# Button.net
KiCad netlist of a schematic drawn in Altium Designer
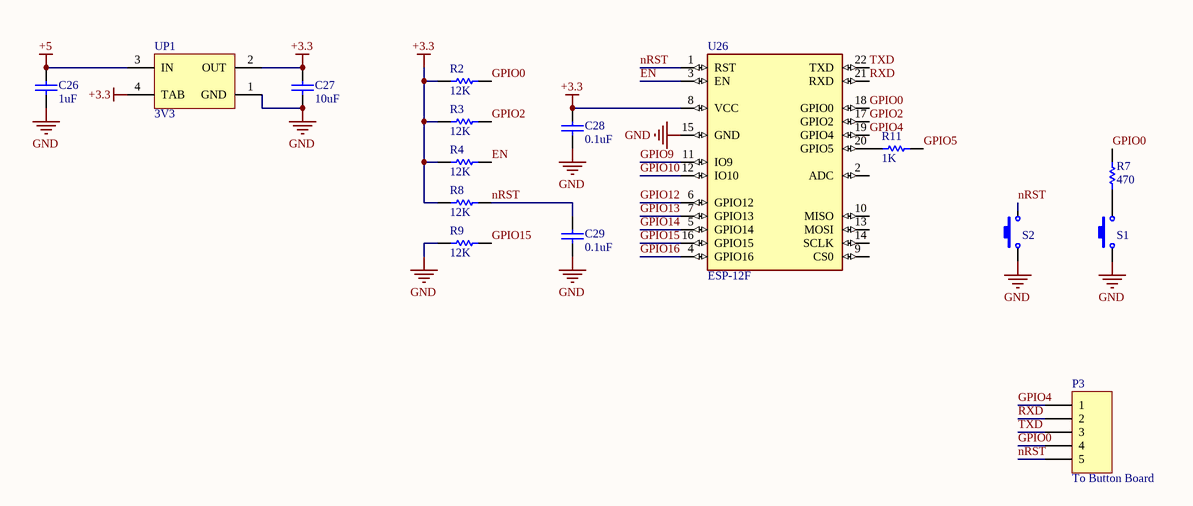
[diagram p0: Button.SchDoc]

(export (version "E")
  (design (tool "Eeschema 10.0.6"))
  (components
    (comp (ref "C26")
      (value "1uF")
      (footprint "CAPC3413X12N")
      (description "CAP 0805")
      (fields (field (name "DESIGNER") "Abbas Basereh"))
      (libsource (lib "Altium") (part "CAP SMD 0805"))
    )
    (comp (ref "C27")
      (value "10uF")
      (footprint "CAPC3413X12N")
      (description "CAP 0805")
      (fields (field (name "DESIGNER") "Abbas Basereh"))
      (libsource (lib "Altium") (part "CAP SMD 0805"))
    )
    (comp (ref "C28")
      (value "0.1uF")
      (footprint "CAPC3413X12N")
      (description "CAP 0805")
      (fields (field (name "DESIGNER") "Abbas Basereh"))
      (libsource (lib "Altium") (part "CAP SMD 0805"))
    )
    (comp (ref "C29")
      (value "0.1uF")
      (footprint "CAPC3413X12N")
      (description "CAP 0805")
      (fields (field (name "DESIGNER") "Abbas Basereh"))
      (libsource (lib "Altium") (part "CAP SMD 0805"))
    )
    (comp (ref "P3")
      (value "To Button Board")
      (footprint "HDR1X5")
      (description "Header, 5-Pin")
      (fields (field (name "PUBLISHER") "Altium Limited"))
      (libsource (lib "Altium") (part "Header 5"))
    )
    (comp (ref "R2")
      (value "12K")
      (footprint "RES0805")
      (description "TOTAL SMD RESISTOR PACK")
      (fields (field (name "DESIGNER") "Abbas Basereh"))
      (libsource (lib "Altium") (part "RES SMD PACKAGE"))
    )
    (comp (ref "R3")
      (value "12K")
      (footprint "RES0805")
      (description "TOTAL SMD RESISTOR PACK")
      (fields (field (name "DESIGNER") "Abbas Basereh"))
      (libsource (lib "Altium") (part "RES SMD PACKAGE"))
    )
    (comp (ref "R4")
      (value "12K")
      (footprint "RES0805")
      (description "TOTAL SMD RESISTOR PACK")
      (fields (field (name "DESIGNER") "Abbas Basereh"))
      (libsource (lib "Altium") (part "RES SMD PACKAGE"))
    )
    (comp (ref "R7")
      (value "470")
      (footprint "RES0805")
      (description "TOTAL SMD RESISTOR PACK")
      (fields (field (name "DESIGNER") "Abbas Basereh"))
      (libsource (lib "Altium") (part "RES SMD PACKAGE"))
    )
    (comp (ref "R8")
      (value "12K")
      (footprint "RES0805")
      (description "TOTAL SMD RESISTOR PACK")
      (fields (field (name "DESIGNER") "Abbas Basereh"))
      (libsource (lib "Altium") (part "RES SMD PACKAGE"))
    )
    (comp (ref "R9")
      (value "12K")
      (footprint "RES0805")
      (description "TOTAL SMD RESISTOR PACK")
      (fields (field (name "DESIGNER") "Abbas Basereh"))
      (libsource (lib "Altium") (part "RES SMD PACKAGE"))
    )
    (comp (ref "R11")
      (value "1K")
      (footprint "RES0805")
      (description "TOTAL SMD RESISTOR PACK")
      (fields (field (name "DESIGNER") "Abbas Basereh"))
      (libsource (lib "Altium") (part "RES SMD PACKAGE"))
    )
    (comp (ref "S1")
      (value "Switch PB")
      (footprint "SW-PB")
      (description "Push Button Switch")
      (libsource (lib "Altium") (part "Switch PB"))
    )
    (comp (ref "S2")
      (value "Switch PB")
      (footprint "SW-PB")
      (description "Push Button Switch")
      (libsource (lib "Altium") (part "Switch PB"))
    )
    (comp (ref "U26")
      (value "ESP-12F")
      (footprint "ESP-12F")
      (description "WiFi Module")
      (fields (field (name "MF") "AI-Thinker"))
      (libsource (lib "ESP-12F") (part "ESP-12F"))
    )
    (comp (ref "UP1")
      (value "3V3")
      (footprint "SOT223")
      (description "x.x Volt, 800mA Low-Dropout Linear Regulator, 4-pin SOT-223")
      (fields (field (name "DESIGNER") "Ali Hafizi"))
      (libsource (lib "Altium") (part "AMS1117-x.x"))
    )
  )
  (nets
    (net (code "1") (name "+3.3") (class "Default")
      (node (ref "C27") (pin "1") (pinfunction "1_1") (pintype "passive"))
      (node (ref "C28") (pin "1") (pinfunction "1_1") (pintype "passive"))
      (node (ref "R2") (pin "1") (pinfunction "1_1") (pintype "passive"))
      (node (ref "R3") (pin "1") (pinfunction "1_1") (pintype "passive"))
      (node (ref "R4") (pin "1") (pinfunction "1_1") (pintype "passive"))
      (node (ref "R8") (pin "1") (pinfunction "1_1") (pintype "passive"))
      (node (ref "U26") (pin "8") (pinfunction "VCC_8") (pintype "bidirectional"))
      (node (ref "UP1") (pin "2") (pinfunction "OUT_2") (pintype "power_in"))
      (node (ref "UP1") (pin "4") (pinfunction "TAB_4") (pintype "power_in"))
    )
    (net (code "2") (name "+5") (class "Default")
      (node (ref "C26") (pin "1") (pinfunction "1_1") (pintype "passive"))
      (node (ref "UP1") (pin "3") (pinfunction "IN_3") (pintype "power_in"))
    )
    (net (code "3") (name "/EN") (class "Default")
      (node (ref "R4") (pin "2") (pinfunction "2_2") (pintype "passive"))
      (node (ref "U26") (pin "3") (pinfunction "EN_3") (pintype "bidirectional"))
    )
    (net (code "4") (name "/GPIO0") (class "Default")
      (node (ref "P3") (pin "4") (pinfunction "4_4") (pintype "passive"))
      (node (ref "R2") (pin "2") (pinfunction "2_2") (pintype "passive"))
      (node (ref "R7") (pin "1") (pinfunction "1_1") (pintype "passive"))
      (node (ref "U26") (pin "18") (pinfunction "GPIO0_18") (pintype "bidirectional"))
    )
    (net (code "5") (name "/GPIO2") (class "Default")
      (node (ref "R3") (pin "2") (pinfunction "2_2") (pintype "passive"))
      (node (ref "U26") (pin "17") (pinfunction "GPIO2_17") (pintype "bidirectional"))
    )
    (net (code "6") (name "/GPIO4") (class "Default")
      (node (ref "P3") (pin "1") (pinfunction "1_1") (pintype "passive"))
      (node (ref "U26") (pin "19") (pinfunction "GPIO4_19") (pintype "bidirectional"))
    )
    (net (code "7") (name "/GPIO5") (class "Default")
      (node (ref "R11") (pin "2") (pinfunction "2_2") (pintype "passive"))
    )
    (net (code "8") (name "/GPIO9") (class "Default")
      (node (ref "U26") (pin "11") (pinfunction "IO9_11") (pintype "bidirectional"))
    )
    (net (code "9") (name "/GPIO10") (class "Default")
      (node (ref "U26") (pin "12") (pinfunction "IO10_12") (pintype "bidirectional"))
    )
    (net (code "10") (name "/GPIO12") (class "Default")
      (node (ref "U26") (pin "6") (pinfunction "GPIO12_6") (pintype "bidirectional"))
    )
    (net (code "11") (name "/GPIO13") (class "Default")
      (node (ref "U26") (pin "7") (pinfunction "GPIO13_7") (pintype "bidirectional"))
    )
    (net (code "12") (name "/GPIO14") (class "Default")
      (node (ref "U26") (pin "5") (pinfunction "GPIO14_5") (pintype "bidirectional"))
    )
    (net (code "13") (name "/GPIO15") (class "Default")
      (node (ref "R9") (pin "2") (pinfunction "2_2") (pintype "passive"))
      (node (ref "U26") (pin "16") (pinfunction "GPIO15_16") (pintype "bidirectional"))
    )
    (net (code "14") (name "/GPIO16") (class "Default")
      (node (ref "U26") (pin "4") (pinfunction "GPIO16_4") (pintype "bidirectional"))
    )
    (net (code "15") (name "/RXD") (class "Default")
      (node (ref "P3") (pin "2") (pinfunction "2_2") (pintype "passive"))
      (node (ref "U26") (pin "21") (pinfunction "RXD_21") (pintype "bidirectional"))
    )
    (net (code "16") (name "/TXD") (class "Default")
      (node (ref "P3") (pin "3") (pinfunction "3_3") (pintype "passive"))
      (node (ref "U26") (pin "22") (pinfunction "TXD_22") (pintype "bidirectional"))
    )
    (net (code "17") (name "/nRST") (class "Default")
      (node (ref "C29") (pin "2") (pinfunction "2_2") (pintype "passive"))
      (node (ref "P3") (pin "5") (pinfunction "5_5") (pintype "passive"))
      (node (ref "R8") (pin "2") (pinfunction "2_2") (pintype "passive"))
      (node (ref "S2") (pin "2") (pinfunction "2_2") (pintype "passive"))
      (node (ref "U26") (pin "1") (pinfunction "RST_1") (pintype "bidirectional"))
    )
    (net (code "18") (name "GND") (class "Default")
      (node (ref "C26") (pin "2") (pinfunction "2_2") (pintype "passive"))
      (node (ref "C27") (pin "2") (pinfunction "2_2") (pintype "passive"))
      (node (ref "C28") (pin "2") (pinfunction "2_2") (pintype "passive"))
      (node (ref "C29") (pin "1") (pinfunction "1_1") (pintype "passive"))
      (node (ref "R9") (pin "1") (pinfunction "1_1") (pintype "passive"))
      (node (ref "S1") (pin "1") (pinfunction "1_1") (pintype "passive"))
      (node (ref "S2") (pin "1") (pinfunction "1_1") (pintype "passive"))
      (node (ref "U26") (pin "15") (pinfunction "GND_15") (pintype "bidirectional"))
      (node (ref "UP1") (pin "1") (pinfunction "GND_1") (pintype "power_in"))
    )
    (net (code "19") (name "Net-(R7-Pad2)") (class "Default")
      (node (ref "R7") (pin "2") (pinfunction "2_2") (pintype "passive"))
      (node (ref "S1") (pin "2") (pinfunction "2_2") (pintype "passive"))
    )
    (net (code "20") (name "Net-(U26-GPIO5)") (class "Default")
      (node (ref "R11") (pin "1") (pinfunction "1_1") (pintype "passive"))
      (node (ref "U26") (pin "20") (pinfunction "GPIO5_20") (pintype "bidirectional"))
    )
    (net (code "21") (name "unconnected-(U26-ADC-Pad2)") (class "Default")
      (node (ref "U26") (pin "2") (pinfunction "ADC_2") (pintype "bidirectional"))
    )
    (net (code "22") (name "unconnected-(U26-CS0-Pad9)") (class "Default")
      (node (ref "U26") (pin "9") (pinfunction "CS0_9") (pintype "bidirectional"))
    )
    (net (code "23") (name "unconnected-(U26-MISO-Pad10)") (class "Default")
      (node (ref "U26") (pin "10") (pinfunction "MISO_10") (pintype "bidirectional"))
    )
    (net (code "24") (name "unconnected-(U26-MOSI-Pad13)") (class "Default")
      (node (ref "U26") (pin "13") (pinfunction "MOSI_13") (pintype "bidirectional"))
    )
    (net (code "25") (name "unconnected-(U26-SCLK-Pad14)") (class "Default")
      (node (ref "U26") (pin "14") (pinfunction "SCLK_14") (pintype "bidirectional"))
    )
  )
)
